# Qwiic_OLED_1_3in.net
KiCad netlist of a schematic drawn in EAGLE
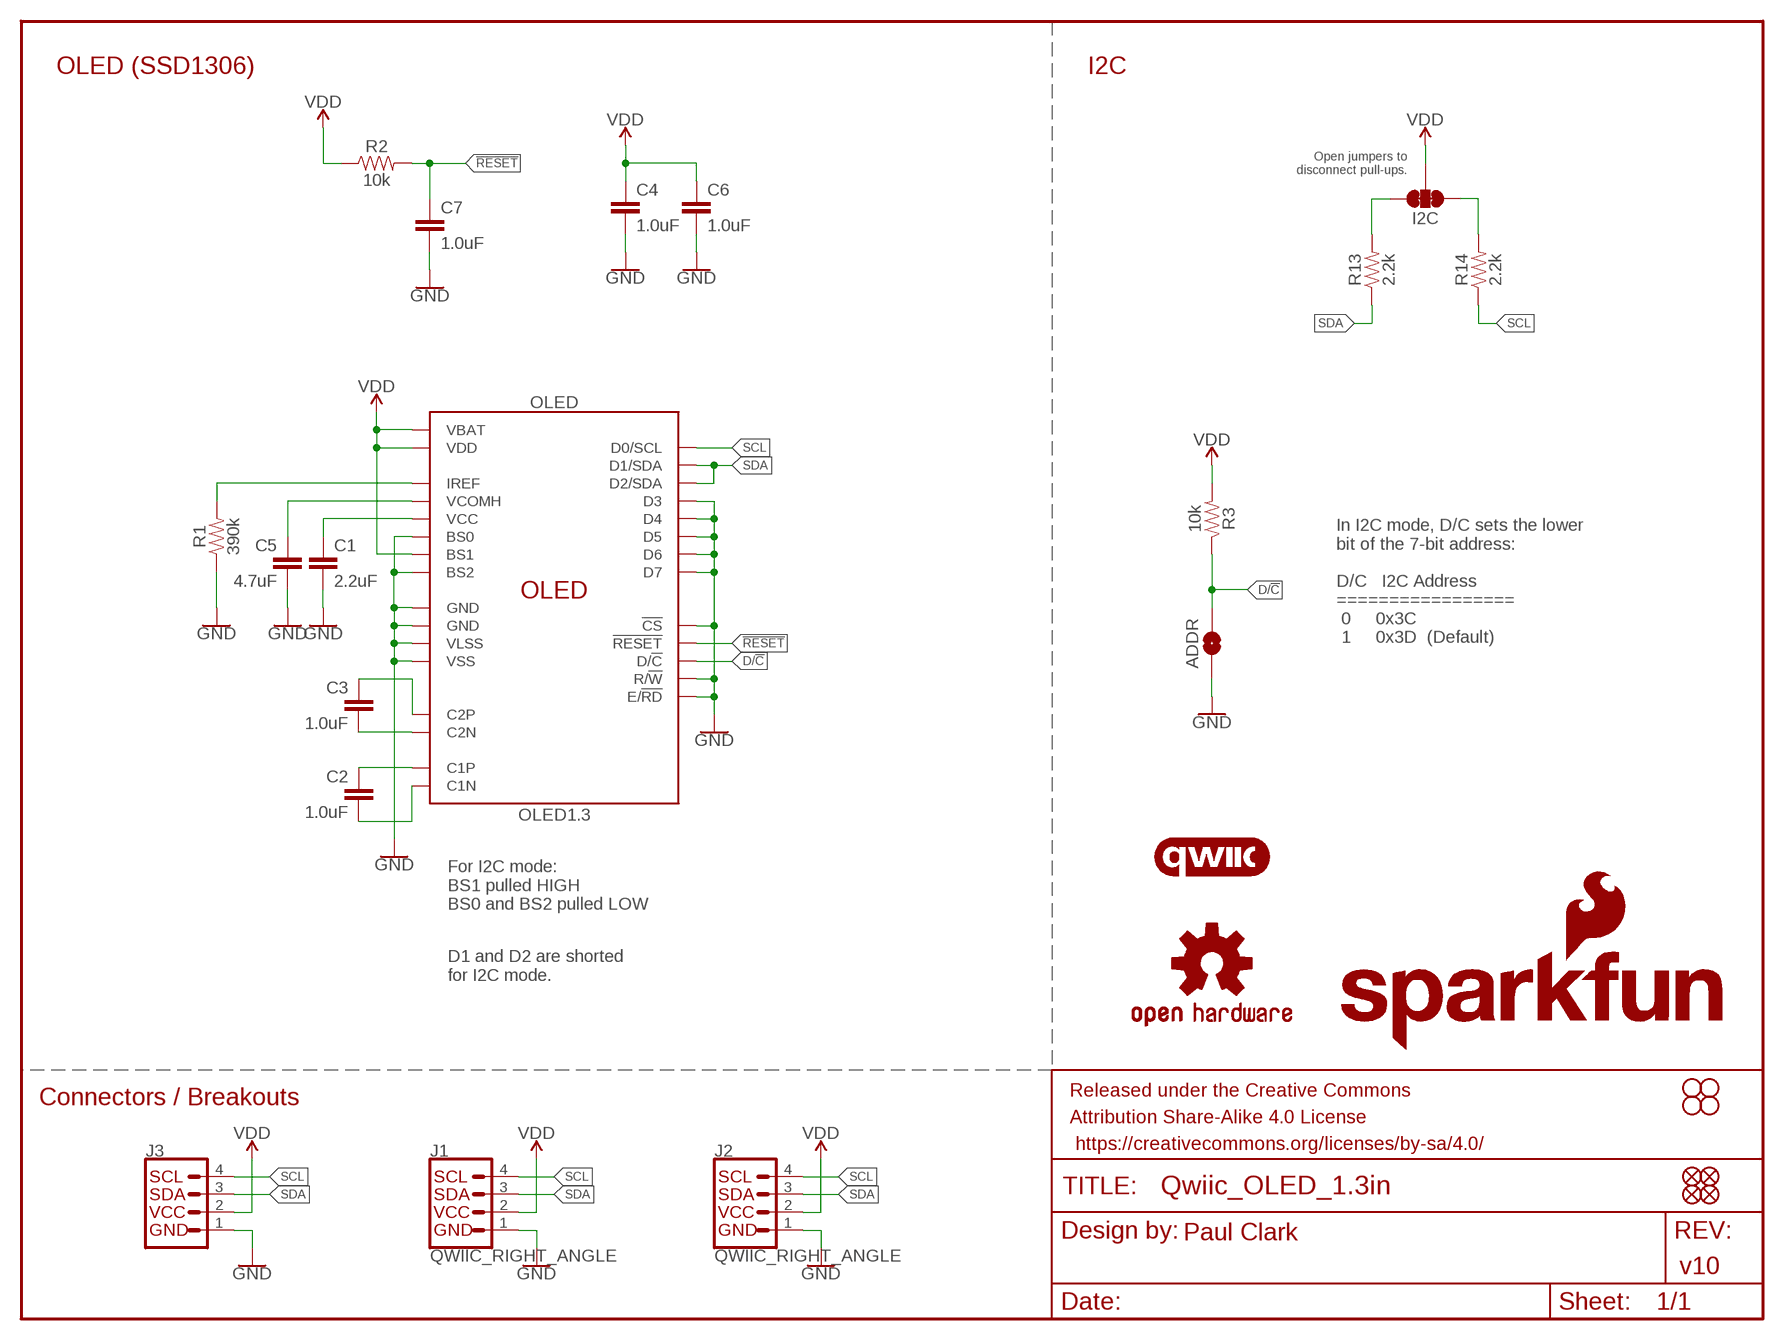
[diagram p0: schematic, sheet 1]

(export (version "E")
  (design (tool "Eeschema 10.0.6"))
  (components
    (comp (ref "ADDR")
      (value "JUMPER-SMT_2_NO_SILK")
      (footprint "eagle-import:SMT-JUMPER_2_NO_SILK")
      (libsource (lib "eagle-import") (part "JUMPER-SMT_2_NO_SILK"))
    )
    (comp (ref "C1")
      (value "2.2uF")
      (footprint "eagle-import:0603")
      (libsource (lib "eagle-import") (part "2.2UF-0603-10V-20%"))
    )
    (comp (ref "C2")
      (value "1.0uF")
      (footprint "eagle-import:0603")
      (libsource (lib "eagle-import") (part "1.0UF-0603-16V-10%-X7R"))
    )
    (comp (ref "C3")
      (value "1.0uF")
      (footprint "eagle-import:0603")
      (libsource (lib "eagle-import") (part "1.0UF-0603-16V-10%-X7R"))
    )
    (comp (ref "C4")
      (value "1.0uF")
      (footprint "eagle-import:0603")
      (libsource (lib "eagle-import") (part "1.0UF-0603-16V-10%-X7R"))
    )
    (comp (ref "C5")
      (value "4.7uF")
      (footprint "eagle-import:0603")
      (libsource (lib "eagle-import") (part "4.7UF-0603-35V-(20%)"))
    )
    (comp (ref "C6")
      (value "1.0uF")
      (footprint "eagle-import:0603")
      (libsource (lib "eagle-import") (part "1.0UF-0603-16V-10%-X7R"))
    )
    (comp (ref "C7")
      (value "1.0uF")
      (footprint "eagle-import:0603")
      (libsource (lib "eagle-import") (part "1.0UF-0603-16V-10%-X7R"))
    )
    (comp (ref "FID1")
      (value "FIDUCIAL1X2")
      (footprint "eagle-import:FIDUCIAL-1X2")
      (libsource (lib "eagle-import") (part "FIDUCIAL1X2"))
    )
    (comp (ref "FID2")
      (value "FIDUCIAL1X2")
      (footprint "eagle-import:FIDUCIAL-1X2")
      (libsource (lib "eagle-import") (part "FIDUCIAL1X2"))
    )
    (comp (ref "FID3")
      (value "FIDUCIAL1X2")
      (footprint "eagle-import:FIDUCIAL-1X2")
      (libsource (lib "eagle-import") (part "FIDUCIAL1X2"))
    )
    (comp (ref "FID4")
      (value "FIDUCIAL1X2")
      (footprint "eagle-import:FIDUCIAL-1X2")
      (libsource (lib "eagle-import") (part "FIDUCIAL1X2"))
    )
    (comp (ref "FRAME1")
      (value "FRAME-LETTER")
      (footprint "eagle-import:CREATIVE_COMMONS")
      (libsource (lib "eagle-import") (part "FRAME-LETTER"))
    )
    (comp (ref "H1")
      (value "STAND-OFF")
      (footprint "eagle-import:STAND-OFF")
      (libsource (lib "eagle-import") (part "STAND-OFF"))
    )
    (comp (ref "H2")
      (value "STAND-OFF")
      (footprint "eagle-import:STAND-OFF")
      (libsource (lib "eagle-import") (part "STAND-OFF"))
    )
    (comp (ref "H3")
      (value "STAND-OFF")
      (footprint "eagle-import:STAND-OFF")
      (libsource (lib "eagle-import") (part "STAND-OFF"))
    )
    (comp (ref "H4")
      (value "STAND-OFF")
      (footprint "eagle-import:STAND-OFF")
      (libsource (lib "eagle-import") (part "STAND-OFF"))
    )
    (comp (ref "I2C")
      (value "JUMPER-SMT_3_2-NC_TRACE_SILK")
      (footprint "eagle-import:SMT-JUMPER_3_2-NC_TRACE_SILK")
      (libsource (lib "eagle-import") (part "JUMPER-SMT_3_2-NC_TRACE_SILK"))
    )
    (comp (ref "J1")
      (value "QWIIC_RIGHT_ANGLE")
      (footprint "eagle-import:JST04_1MM_RA")
      (libsource (lib "eagle-import") (part "QWIIC_CONNECTORJS-1MM"))
    )
    (comp (ref "J2")
      (value "QWIIC_RIGHT_ANGLE")
      (footprint "eagle-import:JST04_1MM_RA")
      (libsource (lib "eagle-import") (part "QWIIC_CONNECTORJS-1MM"))
    )
    (comp (ref "J3")
      (value "I2C_STANDARD_NO_SILK")
      (footprint "eagle-import:1X04_NO_SILK")
      (libsource (lib "eagle-import") (part "I2C_STANDARD_NO_SILK"))
    )
    (comp (ref "LOGO1")
      (value "QWIIC_LOGO_6MM")
      (footprint "eagle-import:QWIIC_6MM")
      (libsource (lib "eagle-import") (part "QWIIC_LOGO_6MM"))
    )
    (comp (ref "LOGO3")
      (value "OSHW-LOGOS")
      (footprint "eagle-import:OSHW-LOGO-S")
      (libsource (lib "eagle-import") (part "OSHW-LOGOS"))
    )
    (comp (ref "LOGO4")
      (value "SFE_LOGO_NAME_FLAME.1_INCH")
      (footprint "eagle-import:SFE_LOGO_NAME_FLAME_.1")
      (libsource (lib "eagle-import") (part "SFE_LOGO_NAME_FLAME.1_INCH"))
    )
    (comp (ref "OLED")
      (value "OLED1.3")
      (footprint "eagle-import:OLED-1.3-128X64")
      (libsource (lib "eagle-import") (part "OLED1.3"))
    )
    (comp (ref "R1")
      (value "390k")
      (footprint "eagle-import:0603")
      (libsource (lib "eagle-import") (part "390KOHM-0603-1/10W-1%"))
    )
    (comp (ref "R2")
      (value "10k")
      (footprint "eagle-import:0603")
      (libsource (lib "eagle-import") (part "10KOHM-0603-1/10W-1%"))
    )
    (comp (ref "R3")
      (value "10k")
      (footprint "eagle-import:0603")
      (libsource (lib "eagle-import") (part "10KOHM-0603-1/10W-1%"))
    )
    (comp (ref "R13")
      (value "2.2k")
      (footprint "eagle-import:0603")
      (libsource (lib "eagle-import") (part "2.2KOHM-0603-1/10W-1%"))
    )
    (comp (ref "R14")
      (value "2.2k")
      (footprint "eagle-import:0603")
      (libsource (lib "eagle-import") (part "2.2KOHM-0603-1/10W-1%"))
    )
  )
  (nets
    (net (code "1") (name "/D{slash}~{C}") (class "Default")
      (node (ref "ADDR") (pin "2") (pinfunction "2_2") (pintype "passive"))
      (node (ref "OLED") (pin "15") (pinfunction "D/~{C}_15") (pintype "bidirectional"))
      (node (ref "R3") (pin "1") (pinfunction "1_1") (pintype "passive"))
    )
    (net (code "2") (name "/~{RESET}") (class "Default")
      (node (ref "C7") (pin "1") (pinfunction "1_1") (pintype "passive"))
      (node (ref "OLED") (pin "14") (pinfunction "~{RESET}_14") (pintype "bidirectional"))
      (node (ref "R2") (pin "2") (pinfunction "2_2") (pintype "passive"))
    )
    (net (code "3") (name "GND") (class "Default")
      (node (ref "ADDR") (pin "1") (pinfunction "1_1") (pintype "passive"))
      (node (ref "C1") (pin "2") (pinfunction "2_2") (pintype "passive"))
      (node (ref "C4") (pin "2") (pinfunction "2_2") (pintype "passive"))
      (node (ref "C5") (pin "2") (pinfunction "2_2") (pintype "passive"))
      (node (ref "C6") (pin "2") (pinfunction "2_2") (pintype "passive"))
      (node (ref "C7") (pin "2") (pinfunction "2_2") (pintype "passive"))
      (node (ref "J1") (pin "1") (pinfunction "1_1") (pintype "power_in"))
      (node (ref "J2") (pin "1") (pinfunction "1_1") (pintype "power_in"))
      (node (ref "J3") (pin "1") (pinfunction "GND_1") (pintype "power_in"))
      (node (ref "OLED") (pin "1") (pinfunction "GND_1") (pintype "bidirectional"))
      (node (ref "OLED") (pin "10") (pinfunction "BS0_10") (pintype "bidirectional"))
      (node (ref "OLED") (pin "12") (pinfunction "BS2_12") (pintype "bidirectional"))
      (node (ref "OLED") (pin "13") (pinfunction "~{CS}_13") (pintype "bidirectional"))
      (node (ref "OLED") (pin "16") (pinfunction "R/~{W}_16") (pintype "bidirectional"))
      (node (ref "OLED") (pin "17") (pinfunction "E/~{RD}_17") (pintype "bidirectional"))
      (node (ref "OLED") (pin "21") (pinfunction "D3_21") (pintype "bidirectional"))
      (node (ref "OLED") (pin "22") (pinfunction "D4_22") (pintype "bidirectional"))
      (node (ref "OLED") (pin "23") (pinfunction "D5_23") (pintype "bidirectional"))
      (node (ref "OLED") (pin "24") (pinfunction "D6_24") (pintype "bidirectional"))
      (node (ref "OLED") (pin "25") (pinfunction "D7_25") (pintype "bidirectional"))
      (node (ref "OLED") (pin "29") (pinfunction "VLSS_29") (pintype "bidirectional"))
      (node (ref "OLED") (pin "30") (pinfunction "GND_30") (pintype "bidirectional"))
      (node (ref "OLED") (pin "8") (pinfunction "VSS_8") (pintype "bidirectional"))
      (node (ref "R1") (pin "1") (pinfunction "1_1") (pintype "passive"))
    )
    (net (code "4") (name "Net-(I2C-Pad1)") (class "Default")
      (node (ref "I2C") (pin "1") (pinfunction "1_1") (pintype "passive"))
      (node (ref "R14") (pin "2") (pinfunction "2_2") (pintype "passive"))
    )
    (net (code "5") (name "Net-(I2C-Pad3)") (class "Default")
      (node (ref "I2C") (pin "3") (pinfunction "3_3") (pintype "passive"))
      (node (ref "R13") (pin "2") (pinfunction "2_2") (pintype "passive"))
    )
    (net (code "6") (name "Net-(OLED-C1N)") (class "Default")
      (node (ref "C2") (pin "2") (pinfunction "2_2") (pintype "passive"))
      (node (ref "OLED") (pin "5") (pinfunction "C1N_5") (pintype "bidirectional"))
    )
    (net (code "7") (name "Net-(OLED-C1P)") (class "Default")
      (node (ref "C2") (pin "1") (pinfunction "1_1") (pintype "passive"))
      (node (ref "OLED") (pin "4") (pinfunction "C1P_4") (pintype "bidirectional"))
    )
    (net (code "8") (name "Net-(OLED-C2N)") (class "Default")
      (node (ref "C3") (pin "2") (pinfunction "2_2") (pintype "passive"))
      (node (ref "OLED") (pin "3") (pinfunction "C2N_3") (pintype "bidirectional"))
    )
    (net (code "9") (name "Net-(OLED-C2P)") (class "Default")
      (node (ref "C3") (pin "1") (pinfunction "1_1") (pintype "passive"))
      (node (ref "OLED") (pin "2") (pinfunction "C2P_2") (pintype "bidirectional"))
    )
    (net (code "10") (name "Net-(OLED-IREF)") (class "Default")
      (node (ref "OLED") (pin "26") (pinfunction "IREF_26") (pintype "bidirectional"))
      (node (ref "R1") (pin "2") (pinfunction "2_2") (pintype "passive"))
    )
    (net (code "11") (name "Net-(OLED-VCC)") (class "Default")
      (node (ref "C1") (pin "1") (pinfunction "1_1") (pintype "passive"))
      (node (ref "OLED") (pin "28") (pinfunction "VCC_28") (pintype "bidirectional"))
    )
    (net (code "12") (name "Net-(OLED-VCOMH)") (class "Default")
      (node (ref "C5") (pin "1") (pinfunction "1_1") (pintype "passive"))
      (node (ref "OLED") (pin "27") (pinfunction "VCOMH_27") (pintype "bidirectional"))
    )
    (net (code "13") (name "SCL") (class "Default")
      (node (ref "J1") (pin "4") (pinfunction "4_4") (pintype "passive"))
      (node (ref "J2") (pin "4") (pinfunction "4_4") (pintype "passive"))
      (node (ref "J3") (pin "4") (pinfunction "SCL_4") (pintype "passive"))
      (node (ref "OLED") (pin "18") (pinfunction "D0/SCL_18") (pintype "bidirectional"))
      (node (ref "R14") (pin "1") (pinfunction "1_1") (pintype "passive"))
    )
    (net (code "14") (name "SDA") (class "Default")
      (node (ref "J1") (pin "3") (pinfunction "3_3") (pintype "passive"))
      (node (ref "J2") (pin "3") (pinfunction "3_3") (pintype "passive"))
      (node (ref "J3") (pin "3") (pinfunction "SDA_3") (pintype "passive"))
      (node (ref "OLED") (pin "19") (pinfunction "D1/SDA_19") (pintype "bidirectional"))
      (node (ref "OLED") (pin "20") (pinfunction "D2/SDA_20") (pintype "bidirectional"))
      (node (ref "R13") (pin "1") (pinfunction "1_1") (pintype "passive"))
    )
    (net (code "15") (name "VDD") (class "Default")
      (node (ref "C4") (pin "1") (pinfunction "1_1") (pintype "passive"))
      (node (ref "C6") (pin "1") (pinfunction "1_1") (pintype "passive"))
      (node (ref "I2C") (pin "2") (pinfunction "2_2") (pintype "passive"))
      (node (ref "J1") (pin "2") (pinfunction "2_2") (pintype "power_in"))
      (node (ref "J2") (pin "2") (pinfunction "2_2") (pintype "power_in"))
      (node (ref "J3") (pin "2") (pinfunction "VCC_2") (pintype "power_in"))
      (node (ref "OLED") (pin "11") (pinfunction "BS1_11") (pintype "bidirectional"))
      (node (ref "OLED") (pin "6") (pinfunction "VBAT_6") (pintype "bidirectional"))
      (node (ref "OLED") (pin "9") (pinfunction "VDD_9") (pintype "bidirectional"))
      (node (ref "R2") (pin "1") (pinfunction "1_1") (pintype "passive"))
      (node (ref "R3") (pin "2") (pinfunction "2_2") (pintype "passive"))
    )
  )
)
